# JackPots.net
KiCad netlist of a schematic drawn in EAGLE
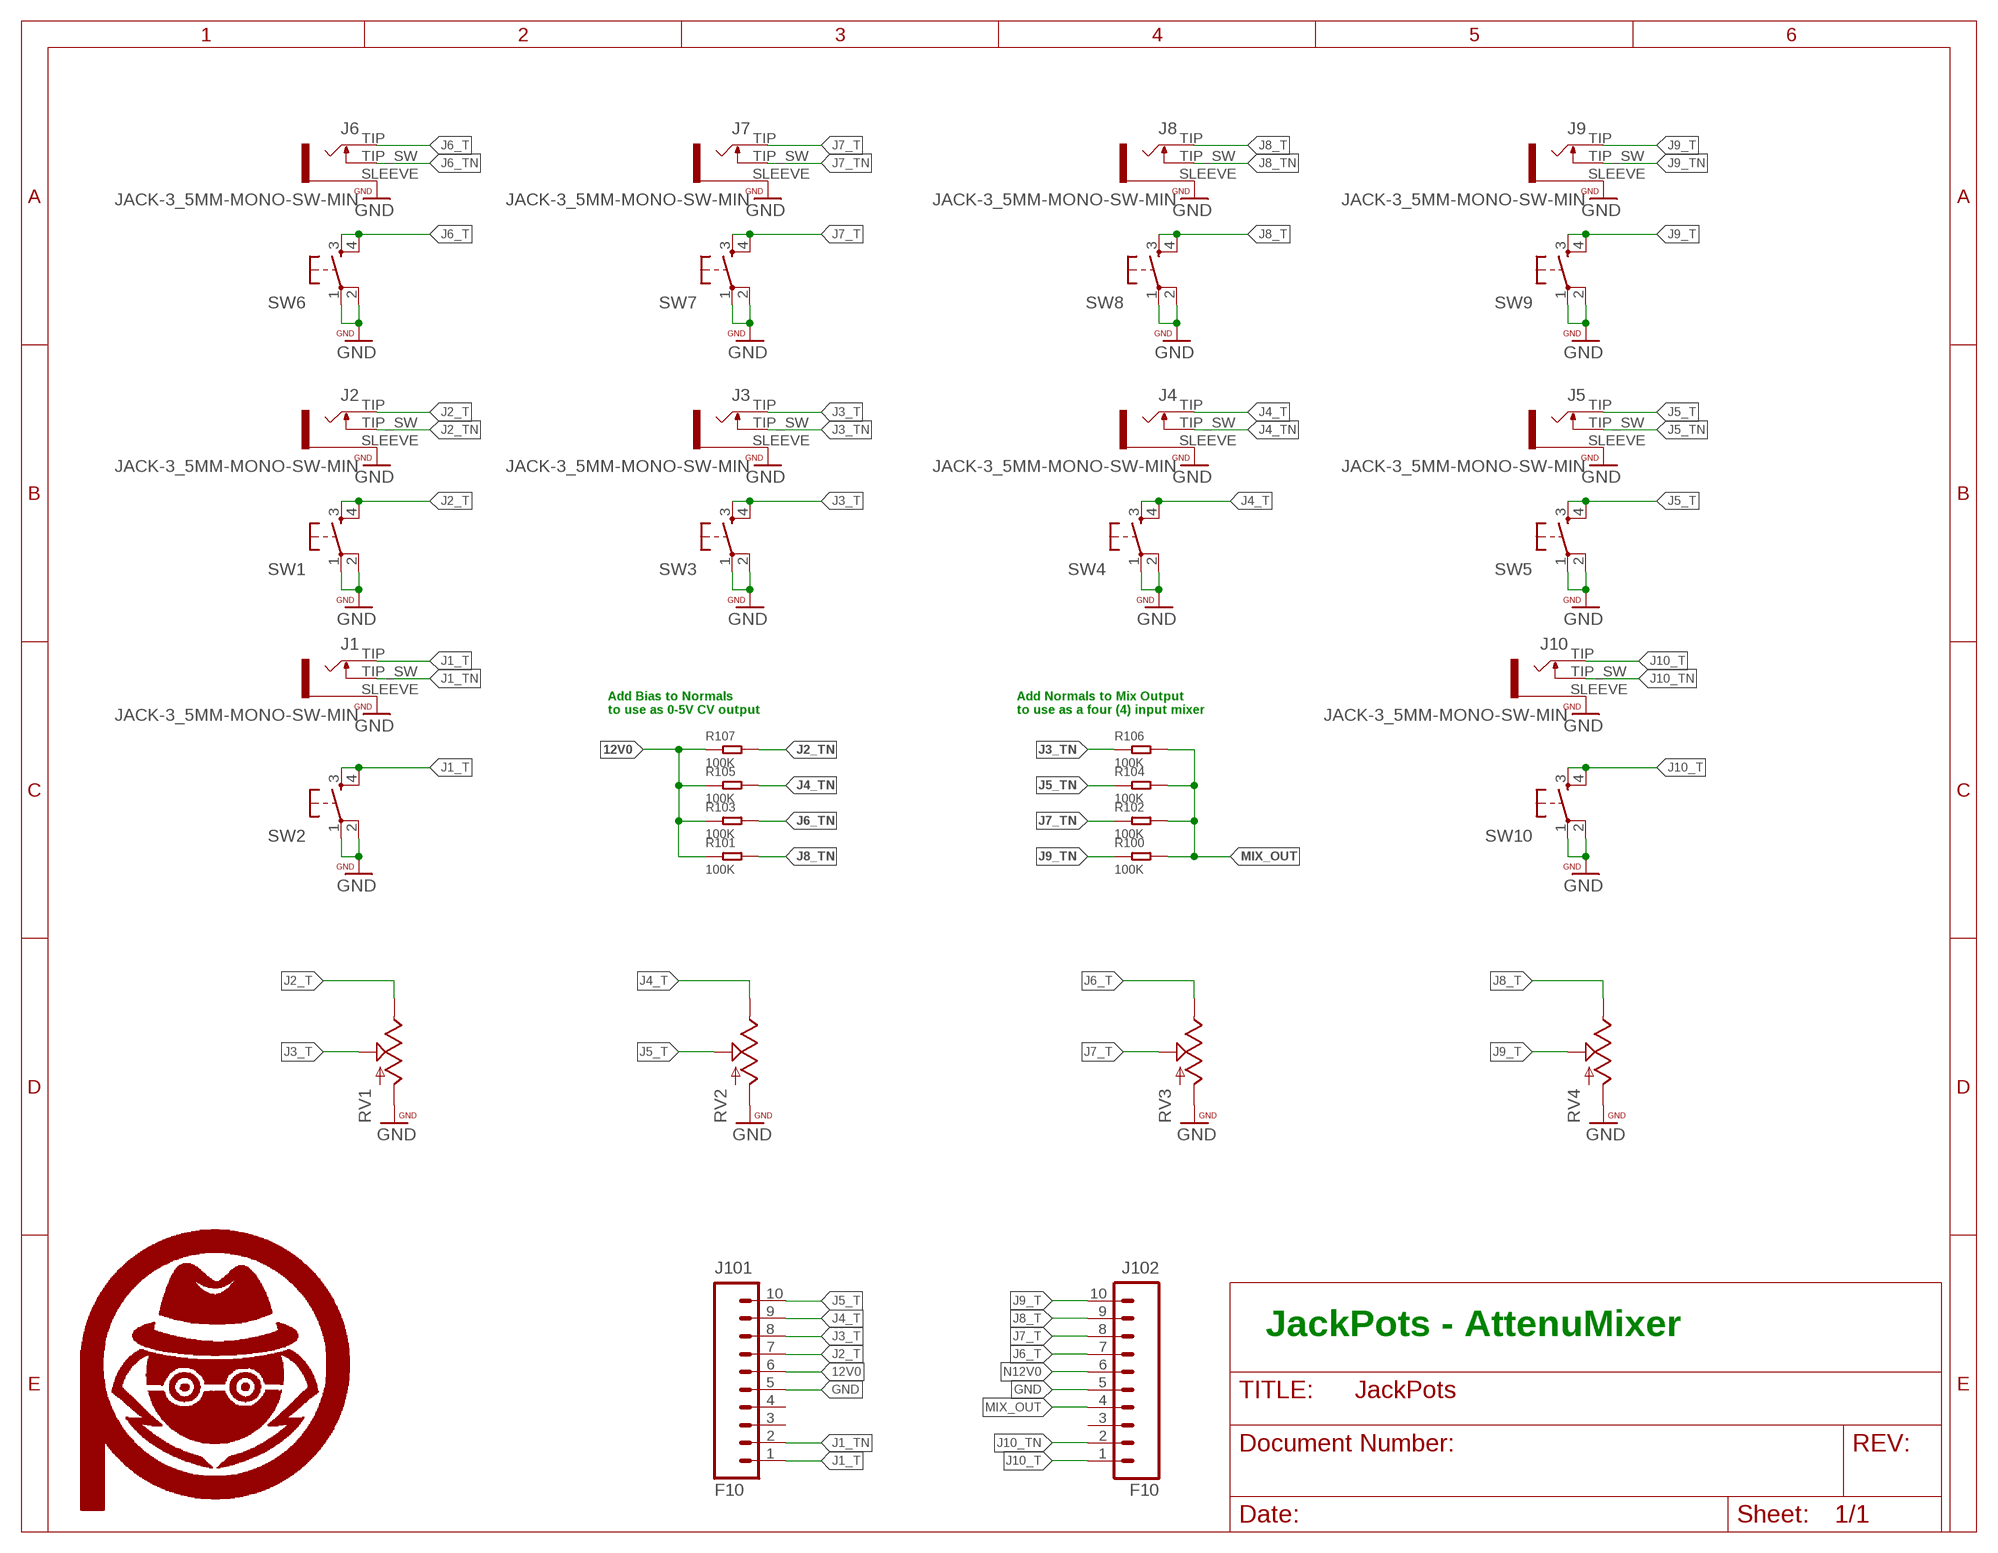
[diagram p0: schematic, sheet 1]

(export (version "E")
  (design (tool "Eeschema 10.0.6"))
  (components
    (comp (ref "$$U$1")
      (value "PA_LOGO_SYMSMALL")
      (footprint "eagle-import:PA_LOGO_AGENT_SMALL_SYM")
      (libsource (lib "eagle-import") (part "PA_LOGO_SYMSMALL"))
    )
    (comp (ref "$$U$100")
      (value "PA_LOGO_SYMMED")
      (footprint "eagle-import:PA_LOGO_AGENT_MED_SYM")
      (libsource (lib "eagle-import") (part "PA_LOGO_SYMMED"))
    )
    (comp (ref "$$U$101")
      (value "PA_LOGO_SYMMED")
      (footprint "eagle-import:PA_LOGO_AGENT_MED_SYM")
      (libsource (lib "eagle-import") (part "PA_LOGO_SYMMED"))
    )
    (comp (ref "J1")
      (value "JACK-3_5MM-MONO-SW-MIN")
      (footprint "eagle-import:WQP_PJ301M-MIN")
      (libsource (lib "eagle-import") (part "JACK-3_5MM-MONO-SW-MIN"))
    )
    (comp (ref "J2")
      (value "JACK-3_5MM-MONO-SW-MIN")
      (footprint "eagle-import:WQP_PJ301M-MIN")
      (libsource (lib "eagle-import") (part "JACK-3_5MM-MONO-SW-MIN"))
    )
    (comp (ref "J3")
      (value "JACK-3_5MM-MONO-SW-MIN")
      (footprint "eagle-import:WQP_PJ301M-MIN")
      (libsource (lib "eagle-import") (part "JACK-3_5MM-MONO-SW-MIN"))
    )
    (comp (ref "J4")
      (value "JACK-3_5MM-MONO-SW-MIN")
      (footprint "eagle-import:WQP_PJ301M-MIN")
      (libsource (lib "eagle-import") (part "JACK-3_5MM-MONO-SW-MIN"))
    )
    (comp (ref "J5")
      (value "JACK-3_5MM-MONO-SW-MIN")
      (footprint "eagle-import:WQP_PJ301M-MIN")
      (libsource (lib "eagle-import") (part "JACK-3_5MM-MONO-SW-MIN"))
    )
    (comp (ref "J6")
      (value "JACK-3_5MM-MONO-SW-MIN")
      (footprint "eagle-import:WQP_PJ301M-MIN")
      (libsource (lib "eagle-import") (part "JACK-3_5MM-MONO-SW-MIN"))
    )
    (comp (ref "J7")
      (value "JACK-3_5MM-MONO-SW-MIN")
      (footprint "eagle-import:WQP_PJ301M-MIN")
      (libsource (lib "eagle-import") (part "JACK-3_5MM-MONO-SW-MIN"))
    )
    (comp (ref "J8")
      (value "JACK-3_5MM-MONO-SW-MIN")
      (footprint "eagle-import:WQP_PJ301M-MIN")
      (libsource (lib "eagle-import") (part "JACK-3_5MM-MONO-SW-MIN"))
    )
    (comp (ref "J9")
      (value "JACK-3_5MM-MONO-SW-MIN")
      (footprint "eagle-import:WQP_PJ301M-MIN")
      (libsource (lib "eagle-import") (part "JACK-3_5MM-MONO-SW-MIN"))
    )
    (comp (ref "J10")
      (value "JACK-3_5MM-MONO-SW-MIN")
      (footprint "eagle-import:WQP_PJ301M-MIN")
      (libsource (lib "eagle-import") (part "JACK-3_5MM-MONO-SW-MIN"))
    )
    (comp (ref "J101")
      (value "F10")
      (footprint "eagle-import:1X10_OCTO")
      (libsource (lib "eagle-import") (part "M10SILK_FEMALE_PTH"))
    )
    (comp (ref "J102")
      (value "F10")
      (footprint "eagle-import:1X10_OCTO")
      (libsource (lib "eagle-import") (part "M10SILK_FEMALE_PTH"))
    )
    (comp (ref "R100")
      (value "100K")
      (footprint "eagle-import:R0603")
      (fields (field (name "MPN") "RC0603FR-07100KL"))
      (libsource (lib "eagle-import") (part "SMD-RES-100K-1%-1/10W(0603)"))
    )
    (comp (ref "R101")
      (value "100K")
      (footprint "eagle-import:R0603")
      (fields (field (name "MPN") "RC0603FR-07100KL"))
      (libsource (lib "eagle-import") (part "SMD-RES-100K-1%-1/10W(0603)"))
    )
    (comp (ref "R102")
      (value "100K")
      (footprint "eagle-import:R0603")
      (fields (field (name "MPN") "RC0603FR-07100KL"))
      (libsource (lib "eagle-import") (part "SMD-RES-100K-1%-1/10W(0603)"))
    )
    (comp (ref "R103")
      (value "100K")
      (footprint "eagle-import:R0603")
      (fields (field (name "MPN") "RC0603FR-07100KL"))
      (libsource (lib "eagle-import") (part "SMD-RES-100K-1%-1/10W(0603)"))
    )
    (comp (ref "R104")
      (value "100K")
      (footprint "eagle-import:R0603")
      (fields (field (name "MPN") "RC0603FR-07100KL"))
      (libsource (lib "eagle-import") (part "SMD-RES-100K-1%-1/10W(0603)"))
    )
    (comp (ref "R105")
      (value "100K")
      (footprint "eagle-import:R0603")
      (fields (field (name "MPN") "RC0603FR-07100KL"))
      (libsource (lib "eagle-import") (part "SMD-RES-100K-1%-1/10W(0603)"))
    )
    (comp (ref "R106")
      (value "100K")
      (footprint "eagle-import:R0603")
      (fields (field (name "MPN") "RC0603FR-07100KL"))
      (libsource (lib "eagle-import") (part "SMD-RES-100K-1%-1/10W(0603)"))
    )
    (comp (ref "R107")
      (value "100K")
      (footprint "eagle-import:R0603")
      (fields (field (name "MPN") "RC0603FR-07100KL"))
      (libsource (lib "eagle-import") (part "SMD-RES-100K-1%-1/10W(0603)"))
    )
    (comp (ref "RV1")
      (value "POT")
      (footprint "eagle-import:ALPS_POT")
      (libsource (lib "eagle-import") (part "POT"))
    )
    (comp (ref "RV2")
      (value "POT")
      (footprint "eagle-import:ALPS_POT")
      (libsource (lib "eagle-import") (part "POT"))
    )
    (comp (ref "RV3")
      (value "POT")
      (footprint "eagle-import:ALPS_POT")
      (libsource (lib "eagle-import") (part "POT"))
    )
    (comp (ref "RV4")
      (value "POT")
      (footprint "eagle-import:ALPS_POT")
      (libsource (lib "eagle-import") (part "POT"))
    )
    (comp (ref "SW1")
      (value "TAC_SWITCHPTH")
      (footprint "eagle-import:TACTILE-PTH")
      (libsource (lib "eagle-import") (part "TAC_SWITCHPTH"))
    )
    (comp (ref "SW2")
      (value "TAC_SWITCHPTH")
      (footprint "eagle-import:TACTILE-PTH")
      (libsource (lib "eagle-import") (part "TAC_SWITCHPTH"))
    )
    (comp (ref "SW3")
      (value "TAC_SWITCHPTH")
      (footprint "eagle-import:TACTILE-PTH")
      (libsource (lib "eagle-import") (part "TAC_SWITCHPTH"))
    )
    (comp (ref "SW4")
      (value "TAC_SWITCHPTH")
      (footprint "eagle-import:TACTILE-PTH")
      (libsource (lib "eagle-import") (part "TAC_SWITCHPTH"))
    )
    (comp (ref "SW5")
      (value "TAC_SWITCHPTH")
      (footprint "eagle-import:TACTILE-PTH")
      (libsource (lib "eagle-import") (part "TAC_SWITCHPTH"))
    )
    (comp (ref "SW6")
      (value "TAC_SWITCHPTH")
      (footprint "eagle-import:TACTILE-PTH")
      (libsource (lib "eagle-import") (part "TAC_SWITCHPTH"))
    )
    (comp (ref "SW7")
      (value "TAC_SWITCHPTH")
      (footprint "eagle-import:TACTILE-PTH")
      (libsource (lib "eagle-import") (part "TAC_SWITCHPTH"))
    )
    (comp (ref "SW8")
      (value "TAC_SWITCHPTH")
      (footprint "eagle-import:TACTILE-PTH")
      (libsource (lib "eagle-import") (part "TAC_SWITCHPTH"))
    )
    (comp (ref "SW9")
      (value "TAC_SWITCHPTH")
      (footprint "eagle-import:TACTILE-PTH")
      (libsource (lib "eagle-import") (part "TAC_SWITCHPTH"))
    )
    (comp (ref "SW10")
      (value "TAC_SWITCHPTH")
      (footprint "eagle-import:TACTILE-PTH")
      (libsource (lib "eagle-import") (part "TAC_SWITCHPTH"))
    )
  )
  (nets
    (net (code "1") (name "12V0") (class "Default")
      (node (ref "J101") (pin "6") (pinfunction "6_6") (pintype "passive"))
      (node (ref "R101") (pin "1") (pinfunction "1_1") (pintype "passive"))
      (node (ref "R103") (pin "1") (pinfunction "1_1") (pintype "passive"))
      (node (ref "R105") (pin "1") (pinfunction "1_1") (pintype "passive"))
      (node (ref "R107") (pin "1") (pinfunction "1_1") (pintype "passive"))
    )
    (net (code "2") (name "GND") (class "Default")
      (node (ref "J1") (pin "SLEEVE") (pinfunction "SLEEVE_SLEEVE") (pintype "passive"))
      (node (ref "J10") (pin "SLEEVE") (pinfunction "SLEEVE_SLEEVE") (pintype "passive"))
      (node (ref "J101") (pin "5") (pinfunction "5_5") (pintype "passive"))
      (node (ref "J102") (pin "5") (pinfunction "5_5") (pintype "passive"))
      (node (ref "J2") (pin "SLEEVE") (pinfunction "SLEEVE_SLEEVE") (pintype "passive"))
      (node (ref "J3") (pin "SLEEVE") (pinfunction "SLEEVE_SLEEVE") (pintype "passive"))
      (node (ref "J4") (pin "SLEEVE") (pinfunction "SLEEVE_SLEEVE") (pintype "passive"))
      (node (ref "J5") (pin "SLEEVE") (pinfunction "SLEEVE_SLEEVE") (pintype "passive"))
      (node (ref "J6") (pin "SLEEVE") (pinfunction "SLEEVE_SLEEVE") (pintype "passive"))
      (node (ref "J7") (pin "SLEEVE") (pinfunction "SLEEVE_SLEEVE") (pintype "passive"))
      (node (ref "J8") (pin "SLEEVE") (pinfunction "SLEEVE_SLEEVE") (pintype "passive"))
      (node (ref "J9") (pin "SLEEVE") (pinfunction "SLEEVE_SLEEVE") (pintype "passive"))
      (node (ref "RV1") (pin "P$3") (pinfunction "1_P$3") (pintype "passive"))
      (node (ref "RV2") (pin "P$3") (pinfunction "1_P$3") (pintype "passive"))
      (node (ref "RV3") (pin "P$3") (pinfunction "1_P$3") (pintype "passive"))
      (node (ref "RV4") (pin "P$3") (pinfunction "1_P$3") (pintype "passive"))
      (node (ref "SW1") (pin "1") (pinfunction "1_1") (pintype "passive"))
      (node (ref "SW1") (pin "2") (pinfunction "2_2") (pintype "passive"))
      (node (ref "SW10") (pin "1") (pinfunction "1_1") (pintype "passive"))
      (node (ref "SW10") (pin "2") (pinfunction "2_2") (pintype "passive"))
      (node (ref "SW2") (pin "1") (pinfunction "1_1") (pintype "passive"))
      (node (ref "SW2") (pin "2") (pinfunction "2_2") (pintype "passive"))
      (node (ref "SW3") (pin "1") (pinfunction "1_1") (pintype "passive"))
      (node (ref "SW3") (pin "2") (pinfunction "2_2") (pintype "passive"))
      (node (ref "SW4") (pin "1") (pinfunction "1_1") (pintype "passive"))
      (node (ref "SW4") (pin "2") (pinfunction "2_2") (pintype "passive"))
      (node (ref "SW5") (pin "1") (pinfunction "1_1") (pintype "passive"))
      (node (ref "SW5") (pin "2") (pinfunction "2_2") (pintype "passive"))
      (node (ref "SW6") (pin "1") (pinfunction "1_1") (pintype "passive"))
      (node (ref "SW6") (pin "2") (pinfunction "2_2") (pintype "passive"))
      (node (ref "SW7") (pin "1") (pinfunction "1_1") (pintype "passive"))
      (node (ref "SW7") (pin "2") (pinfunction "2_2") (pintype "passive"))
      (node (ref "SW8") (pin "1") (pinfunction "1_1") (pintype "passive"))
      (node (ref "SW8") (pin "2") (pinfunction "2_2") (pintype "passive"))
      (node (ref "SW9") (pin "1") (pinfunction "1_1") (pintype "passive"))
      (node (ref "SW9") (pin "2") (pinfunction "2_2") (pintype "passive"))
    )
    (net (code "3") (name "J1_T") (class "Default")
      (node (ref "J1") (pin "TIP") (pinfunction "TIP_TIP") (pintype "passive"))
      (node (ref "J101") (pin "1") (pinfunction "1_1") (pintype "passive"))
      (node (ref "SW2") (pin "3") (pinfunction "3_3") (pintype "passive"))
      (node (ref "SW2") (pin "4") (pinfunction "4_4") (pintype "passive"))
    )
    (net (code "4") (name "J1_TN") (class "Default")
      (node (ref "J1") (pin "TIP_SW") (pinfunction "TIP_SW_TIP_SW") (pintype "passive"))
      (node (ref "J101") (pin "2") (pinfunction "2_2") (pintype "passive"))
    )
    (net (code "5") (name "J2_T") (class "Default")
      (node (ref "J101") (pin "7") (pinfunction "7_7") (pintype "passive"))
      (node (ref "J2") (pin "TIP") (pinfunction "TIP_TIP") (pintype "passive"))
      (node (ref "RV1") (pin "P$1") (pinfunction "3_P$1") (pintype "passive"))
      (node (ref "SW1") (pin "3") (pinfunction "3_3") (pintype "passive"))
      (node (ref "SW1") (pin "4") (pinfunction "4_4") (pintype "passive"))
    )
    (net (code "6") (name "J2_TN") (class "Default")
      (node (ref "J2") (pin "TIP_SW") (pinfunction "TIP_SW_TIP_SW") (pintype "passive"))
      (node (ref "R107") (pin "2") (pinfunction "2_2") (pintype "passive"))
    )
    (net (code "7") (name "J3_T") (class "Default")
      (node (ref "J101") (pin "8") (pinfunction "8_8") (pintype "passive"))
      (node (ref "J3") (pin "TIP") (pinfunction "TIP_TIP") (pintype "passive"))
      (node (ref "RV1") (pin "P$2") (pinfunction "2_P$2") (pintype "passive"))
      (node (ref "SW3") (pin "3") (pinfunction "3_3") (pintype "passive"))
      (node (ref "SW3") (pin "4") (pinfunction "4_4") (pintype "passive"))
    )
    (net (code "8") (name "J3_TN") (class "Default")
      (node (ref "J3") (pin "TIP_SW") (pinfunction "TIP_SW_TIP_SW") (pintype "passive"))
      (node (ref "R106") (pin "1") (pinfunction "1_1") (pintype "passive"))
    )
    (net (code "9") (name "J4_T") (class "Default")
      (node (ref "J101") (pin "9") (pinfunction "9_9") (pintype "passive"))
      (node (ref "J4") (pin "TIP") (pinfunction "TIP_TIP") (pintype "passive"))
      (node (ref "RV2") (pin "P$1") (pinfunction "3_P$1") (pintype "passive"))
      (node (ref "SW4") (pin "3") (pinfunction "3_3") (pintype "passive"))
      (node (ref "SW4") (pin "4") (pinfunction "4_4") (pintype "passive"))
    )
    (net (code "10") (name "J4_TN") (class "Default")
      (node (ref "J4") (pin "TIP_SW") (pinfunction "TIP_SW_TIP_SW") (pintype "passive"))
      (node (ref "R105") (pin "2") (pinfunction "2_2") (pintype "passive"))
    )
    (net (code "11") (name "J5_T") (class "Default")
      (node (ref "J101") (pin "10") (pinfunction "10_10") (pintype "passive"))
      (node (ref "J5") (pin "TIP") (pinfunction "TIP_TIP") (pintype "passive"))
      (node (ref "RV2") (pin "P$2") (pinfunction "2_P$2") (pintype "passive"))
      (node (ref "SW5") (pin "3") (pinfunction "3_3") (pintype "passive"))
      (node (ref "SW5") (pin "4") (pinfunction "4_4") (pintype "passive"))
    )
    (net (code "12") (name "J5_TN") (class "Default")
      (node (ref "J5") (pin "TIP_SW") (pinfunction "TIP_SW_TIP_SW") (pintype "passive"))
      (node (ref "R104") (pin "1") (pinfunction "1_1") (pintype "passive"))
    )
    (net (code "13") (name "J6_T") (class "Default")
      (node (ref "J102") (pin "7") (pinfunction "7_7") (pintype "passive"))
      (node (ref "J6") (pin "TIP") (pinfunction "TIP_TIP") (pintype "passive"))
      (node (ref "RV3") (pin "P$1") (pinfunction "3_P$1") (pintype "passive"))
      (node (ref "SW6") (pin "3") (pinfunction "3_3") (pintype "passive"))
      (node (ref "SW6") (pin "4") (pinfunction "4_4") (pintype "passive"))
    )
    (net (code "14") (name "J6_TN") (class "Default")
      (node (ref "J6") (pin "TIP_SW") (pinfunction "TIP_SW_TIP_SW") (pintype "passive"))
      (node (ref "R103") (pin "2") (pinfunction "2_2") (pintype "passive"))
    )
    (net (code "15") (name "J7_T") (class "Default")
      (node (ref "J102") (pin "8") (pinfunction "8_8") (pintype "passive"))
      (node (ref "J7") (pin "TIP") (pinfunction "TIP_TIP") (pintype "passive"))
      (node (ref "RV3") (pin "P$2") (pinfunction "2_P$2") (pintype "passive"))
      (node (ref "SW7") (pin "3") (pinfunction "3_3") (pintype "passive"))
      (node (ref "SW7") (pin "4") (pinfunction "4_4") (pintype "passive"))
    )
    (net (code "16") (name "J7_TN") (class "Default")
      (node (ref "J7") (pin "TIP_SW") (pinfunction "TIP_SW_TIP_SW") (pintype "passive"))
      (node (ref "R102") (pin "1") (pinfunction "1_1") (pintype "passive"))
    )
    (net (code "17") (name "J8_T") (class "Default")
      (node (ref "J102") (pin "9") (pinfunction "9_9") (pintype "passive"))
      (node (ref "J8") (pin "TIP") (pinfunction "TIP_TIP") (pintype "passive"))
      (node (ref "RV4") (pin "P$1") (pinfunction "3_P$1") (pintype "passive"))
      (node (ref "SW8") (pin "3") (pinfunction "3_3") (pintype "passive"))
      (node (ref "SW8") (pin "4") (pinfunction "4_4") (pintype "passive"))
    )
    (net (code "18") (name "J8_TN") (class "Default")
      (node (ref "J8") (pin "TIP_SW") (pinfunction "TIP_SW_TIP_SW") (pintype "passive"))
      (node (ref "R101") (pin "2") (pinfunction "2_2") (pintype "passive"))
    )
    (net (code "19") (name "J9_T") (class "Default")
      (node (ref "J102") (pin "10") (pinfunction "10_10") (pintype "passive"))
      (node (ref "J9") (pin "TIP") (pinfunction "TIP_TIP") (pintype "passive"))
      (node (ref "RV4") (pin "P$2") (pinfunction "2_P$2") (pintype "passive"))
      (node (ref "SW9") (pin "3") (pinfunction "3_3") (pintype "passive"))
      (node (ref "SW9") (pin "4") (pinfunction "4_4") (pintype "passive"))
    )
    (net (code "20") (name "J9_TN") (class "Default")
      (node (ref "J9") (pin "TIP_SW") (pinfunction "TIP_SW_TIP_SW") (pintype "passive"))
      (node (ref "R100") (pin "1") (pinfunction "1_1") (pintype "passive"))
    )
    (net (code "21") (name "J10_T") (class "Default")
      (node (ref "J10") (pin "TIP") (pinfunction "TIP_TIP") (pintype "passive"))
      (node (ref "J102") (pin "1") (pinfunction "1_1") (pintype "passive"))
      (node (ref "SW10") (pin "3") (pinfunction "3_3") (pintype "passive"))
      (node (ref "SW10") (pin "4") (pinfunction "4_4") (pintype "passive"))
    )
    (net (code "22") (name "J10_TN") (class "Default")
      (node (ref "J10") (pin "TIP_SW") (pinfunction "TIP_SW_TIP_SW") (pintype "passive"))
      (node (ref "J102") (pin "2") (pinfunction "2_2") (pintype "passive"))
    )
    (net (code "23") (name "MIX_OUT") (class "Default")
      (node (ref "J102") (pin "4") (pinfunction "4_4") (pintype "passive"))
      (node (ref "R100") (pin "2") (pinfunction "2_2") (pintype "passive"))
      (node (ref "R102") (pin "2") (pinfunction "2_2") (pintype "passive"))
      (node (ref "R104") (pin "2") (pinfunction "2_2") (pintype "passive"))
      (node (ref "R106") (pin "2") (pinfunction "2_2") (pintype "passive"))
    )
    (net (code "24") (name "N12V0") (class "Default")
      (node (ref "J102") (pin "6") (pinfunction "6_6") (pintype "passive"))
    )
    (net (code "25") (name "unconnected-(J101-Pad3)") (class "Default")
      (node (ref "J101") (pin "3") (pinfunction "3_3") (pintype "passive"))
    )
    (net (code "26") (name "unconnected-(J101-Pad4)") (class "Default")
      (node (ref "J101") (pin "4") (pinfunction "4_4") (pintype "passive"))
    )
    (net (code "27") (name "unconnected-(J102-Pad3)") (class "Default")
      (node (ref "J102") (pin "3") (pinfunction "3_3") (pintype "passive"))
    )
  )
)
